# SCH.net
KiCad netlist of a schematic drawn in Altium Designer
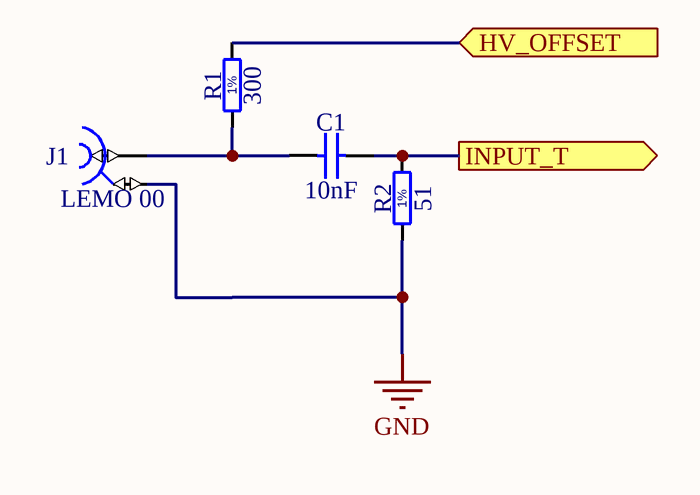
[diagram p0: SCH.SchDoc]

(export (version "E")
  (design (tool "Eeschema 10.0.6"))
  (components
    (comp (ref "C1")
      (value "10nF")
      (footprint "CAPC2012X135N")
      (description "Non-polarised capacitor")
      (fields
        (field (name "PART NUMBER") "CC0805_10NF_50V_10%_X7R")
        (field (name "VOLTAGE") "50V")
        (field (name "AUTHOR") "CERN DEM JLC")
      )
      (libsource (lib "Capacitors") (part "Capacitor - non polarized"))
    )
    (comp (ref "J1")
      (value "LEMO 00")
      (footprint "LEMO_EPA.00.250.NTN")
      (fields
        (field (name "PART NUMBER") "LEMO_EPA.00.250.NTN")
        (field (name "MANUFACTURER") "LEMO")
        (field (name "MANUFACTURER PART NUMBER") "EPA.00.250.NTN")
        (field (name "AUTHOR") "CERN DEM JLC")
      )
      (libsource (lib "Connectors") (part "Coax_1Female_1Shield"))
    )
    (comp (ref "R1")
      (value "300")
      (footprint "RESC2012X60N")
      (description "Resistor - 1%")
      (fields
        (field (name "PART NUMBER") "R0805_300R_1%_0.125W_100PPM")
        (field (name "POWER") "0.125W")
        (field (name "AUTHOR") "CERN DEM JLC")
      )
      (libsource (lib "Resistors") (part "Resistor - 1%"))
    )
    (comp (ref "R2")
      (value "51")
      (footprint "RESC2012X60N")
      (description "Resistor - 1%")
      (fields
        (field (name "PART NUMBER") "R0805_51R_1%_0.125W_100PPM")
        (field (name "POWER") "0.125W")
        (field (name "AUTHOR") "CERN DEM JLC")
      )
      (libsource (lib "Resistors") (part "Resistor - 1%"))
    )
  )
  (nets
    (net (code "1") (name "/HV_OFFSET") (class "Default")
      (node (ref "R1") (pin "2") (pinfunction "2_2") (pintype "passive"))
    )
    (net (code "2") (name "/INPUT_T") (class "Default")
      (node (ref "C1") (pin "2") (pinfunction "2_2") (pintype "passive"))
      (node (ref "R2") (pin "2") (pinfunction "2_2") (pintype "passive"))
    )
    (net (code "3") (name "GND") (class "Default")
      (node (ref "J1") (pin "2") (pinfunction "2_2") (pintype "bidirectional"))
      (node (ref "R2") (pin "1") (pinfunction "1_1") (pintype "passive"))
    )
    (net (code "4") (name "Net-(C1-Pad1)") (class "Default")
      (node (ref "C1") (pin "1") (pinfunction "1_1") (pintype "passive"))
      (node (ref "J1") (pin "1") (pinfunction "1_1") (pintype "bidirectional"))
      (node (ref "R1") (pin "1") (pinfunction "1_1") (pintype "passive"))
    )
  )
)
